# Sheet2.net
KiCad netlist of a schematic drawn in Altium Designer
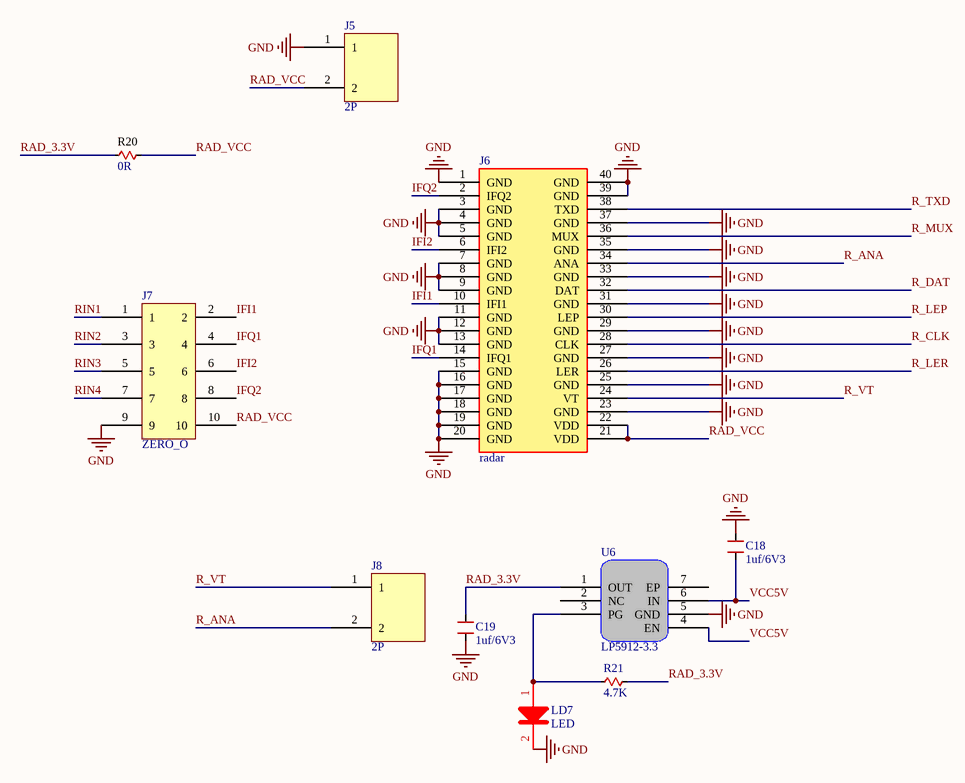
[diagram p0: Sheet2.SchDoc]

(export (version "E")
  (design (tool "Eeschema 10.0.6"))
  (components
    (comp (ref "C18")
      (value "1uf/6V3")
      (footprint "CAP0603")
      (description "Generic Capacitor")
      (libsource (lib "MZ7XB_Fun") (part "CAPACITOR_1UF"))
    )
    (comp (ref "C19")
      (value "1uf/6V3")
      (footprint "CAP0603")
      (description "Generic Capacitor")
      (libsource (lib "MZ7XB_Fun") (part "CAPACITOR_1UF"))
    )
    (comp (ref "J5") (value "2P") (footprint "2P") (libsource (lib "MZ7XB_Fun") (part "2P")))
    (comp (ref "J6") (value "radar") (footprint "BTB_40P_0.8_G") (libsource (lib "MZ7XB_Fun") (part "radar")))
    (comp (ref "J7") (value "ZERO_O") (footprint "2*5P") (libsource (lib "MZ7XB_Fun") (part "ZERO_O")))
    (comp (ref "J8") (value "2P") (footprint "2P") (libsource (lib "MZ7XB_Fun") (part "2P")))
    (comp (ref "LD7") (value "LED") (footprint "0603D") (libsource (lib "jinrylib") (part "LEDR")))
    (comp (ref "R20")
      (value "0R")
      (footprint "R0603")
      (description "Generic Resistor")
      (libsource (lib "Digilent") (part "RESISTOR"))
    )
    (comp (ref "R21")
      (value "4.7K")
      (footprint "R0603")
      (description "Generic Resistor")
      (libsource (lib "Digilent") (part "RESISTOR"))
    )
    (comp (ref "U6")
      (value "LP5912-3.3")
      (footprint "WSON-6_L2.0-W2.0-P0.65-TL-EP")
      (libsource (lib "MZ7XB_Fun") (part "LP5912-3.3"))
    )
  )
  (nets
    (net (code "1") (name "/IFI1") (class "Default")
      (node (ref "J6") (pin "10") (pinfunction "IFI1_10") (pintype "passive"))
      (node (ref "J7") (pin "2") (pinfunction "2_2") (pintype "passive"))
    )
    (net (code "2") (name "/IFI2") (class "Default")
      (node (ref "J6") (pin "6") (pinfunction "IFI2_6") (pintype "passive"))
      (node (ref "J7") (pin "6") (pinfunction "6_6") (pintype "passive"))
    )
    (net (code "3") (name "/IFQ1") (class "Default")
      (node (ref "J6") (pin "14") (pinfunction "IFQ1_14") (pintype "passive"))
      (node (ref "J7") (pin "4") (pinfunction "4_4") (pintype "passive"))
    )
    (net (code "4") (name "/IFQ2") (class "Default")
      (node (ref "J6") (pin "2") (pinfunction "IFQ2_2") (pintype "passive"))
      (node (ref "J7") (pin "8") (pinfunction "8_8") (pintype "passive"))
    )
    (net (code "5") (name "/RAD_3.3V") (class "Default")
      (node (ref "C19") (pin "1") (pinfunction "1_1") (pintype "passive"))
      (node (ref "R20") (pin "1") (pinfunction "1_1") (pintype "passive"))
      (node (ref "R21") (pin "2") (pinfunction "2_2") (pintype "passive"))
      (node (ref "U6") (pin "1") (pinfunction "OUT_1") (pintype "passive"))
    )
    (net (code "6") (name "/RAD_VCC") (class "Default")
      (node (ref "J5") (pin "2") (pinfunction "2_2") (pintype "passive"))
      (node (ref "J6") (pin "21") (pinfunction "VDD_21") (pintype "passive"))
      (node (ref "J6") (pin "22") (pinfunction "VDD_22") (pintype "passive"))
      (node (ref "J7") (pin "10") (pinfunction "10_10") (pintype "passive"))
      (node (ref "R20") (pin "2") (pinfunction "2_2") (pintype "passive"))
    )
    (net (code "7") (name "/RIN1") (class "Default")
      (node (ref "J7") (pin "1") (pinfunction "1_1") (pintype "passive"))
    )
    (net (code "8") (name "/RIN2") (class "Default")
      (node (ref "J7") (pin "3") (pinfunction "3_3") (pintype "passive"))
    )
    (net (code "9") (name "/RIN3") (class "Default")
      (node (ref "J7") (pin "5") (pinfunction "5_5") (pintype "passive"))
    )
    (net (code "10") (name "/RIN4") (class "Default")
      (node (ref "J7") (pin "7") (pinfunction "7_7") (pintype "passive"))
    )
    (net (code "11") (name "/R_ANA") (class "Default")
      (node (ref "J6") (pin "34") (pinfunction "ANA_34") (pintype "passive"))
      (node (ref "J8") (pin "2") (pinfunction "2_2") (pintype "passive"))
    )
    (net (code "12") (name "/R_CLK") (class "Default")
      (node (ref "J6") (pin "28") (pinfunction "CLK_28") (pintype "passive"))
    )
    (net (code "13") (name "/R_DAT") (class "Default")
      (node (ref "J6") (pin "32") (pinfunction "DAT_32") (pintype "passive"))
    )
    (net (code "14") (name "/R_LEP") (class "Default")
      (node (ref "J6") (pin "30") (pinfunction "LEP_30") (pintype "passive"))
    )
    (net (code "15") (name "/R_LER") (class "Default")
      (node (ref "J6") (pin "26") (pinfunction "LER_26") (pintype "passive"))
    )
    (net (code "16") (name "/R_MUX") (class "Default")
      (node (ref "J6") (pin "36") (pinfunction "MUX_36") (pintype "passive"))
    )
    (net (code "17") (name "/R_TXD") (class "Default")
      (node (ref "J6") (pin "38") (pinfunction "TXD_38") (pintype "passive"))
    )
    (net (code "18") (name "/R_VT") (class "Default")
      (node (ref "J6") (pin "24") (pinfunction "VT_24") (pintype "passive"))
      (node (ref "J8") (pin "1") (pinfunction "1_1") (pintype "passive"))
    )
    (net (code "19") (name "/VCC5V") (class "Default")
      (node (ref "C18") (pin "2") (pinfunction "2_2") (pintype "passive"))
      (node (ref "U6") (pin "4") (pinfunction "EN_4") (pintype "passive"))
      (node (ref "U6") (pin "6") (pinfunction "IN_6") (pintype "passive"))
    )
    (net (code "20") (name "GND") (class "Default")
      (node (ref "C18") (pin "1") (pinfunction "1_1") (pintype "passive"))
      (node (ref "C19") (pin "2") (pinfunction "2_2") (pintype "passive"))
      (node (ref "J5") (pin "1") (pinfunction "1_1") (pintype "passive"))
      (node (ref "J6") (pin "1") (pinfunction "GND_1") (pintype "passive"))
      (node (ref "J6") (pin "11") (pinfunction "GND_11") (pintype "passive"))
      (node (ref "J6") (pin "12") (pinfunction "GND_12") (pintype "passive"))
      (node (ref "J6") (pin "13") (pinfunction "GND_13") (pintype "passive"))
      (node (ref "J6") (pin "15") (pinfunction "GND_15") (pintype "passive"))
      (node (ref "J6") (pin "16") (pinfunction "GND_16") (pintype "passive"))
      (node (ref "J6") (pin "17") (pinfunction "GND_17") (pintype "passive"))
      (node (ref "J6") (pin "18") (pinfunction "GND_18") (pintype "passive"))
      (node (ref "J6") (pin "19") (pinfunction "GND_19") (pintype "passive"))
      (node (ref "J6") (pin "20") (pinfunction "GND_20") (pintype "passive"))
      (node (ref "J6") (pin "23") (pinfunction "GND_23") (pintype "passive"))
      (node (ref "J6") (pin "25") (pinfunction "GND_25") (pintype "passive"))
      (node (ref "J6") (pin "27") (pinfunction "GND_27") (pintype "passive"))
      (node (ref "J6") (pin "29") (pinfunction "GND_29") (pintype "passive"))
      (node (ref "J6") (pin "3") (pinfunction "GND_3") (pintype "passive"))
      (node (ref "J6") (pin "31") (pinfunction "GND_31") (pintype "passive"))
      (node (ref "J6") (pin "33") (pinfunction "GND_33") (pintype "passive"))
      (node (ref "J6") (pin "35") (pinfunction "GND_35") (pintype "passive"))
      (node (ref "J6") (pin "37") (pinfunction "GND_37") (pintype "passive"))
      (node (ref "J6") (pin "39") (pinfunction "GND_39") (pintype "passive"))
      (node (ref "J6") (pin "4") (pinfunction "GND_4") (pintype "passive"))
      (node (ref "J6") (pin "40") (pinfunction "GND_40") (pintype "passive"))
      (node (ref "J6") (pin "5") (pinfunction "GND_5") (pintype "passive"))
      (node (ref "J6") (pin "7") (pinfunction "GND_7") (pintype "passive"))
      (node (ref "J6") (pin "8") (pinfunction "GND_8") (pintype "passive"))
      (node (ref "J6") (pin "9") (pinfunction "GND_9") (pintype "passive"))
      (node (ref "J7") (pin "9") (pinfunction "9_9") (pintype "passive"))
      (node (ref "LD7") (pin "2") (pinfunction "2_2") (pintype "passive"))
      (node (ref "U6") (pin "5") (pinfunction "GND_5") (pintype "passive"))
    )
    (net (code "21") (name "Net-(U6-PG)") (class "Default")
      (node (ref "LD7") (pin "1") (pinfunction "1_1") (pintype "passive"))
      (node (ref "R21") (pin "1") (pinfunction "1_1") (pintype "passive"))
      (node (ref "U6") (pin "3") (pinfunction "PG_3") (pintype "passive"))
    )
    (net (code "22") (name "unconnected-(U6-EP-Pad7)") (class "Default")
      (node (ref "U6") (pin "7") (pinfunction "EP_7") (pintype "passive"))
    )
    (net (code "23") (name "unconnected-(U6-NC-Pad2)") (class "Default")
      (node (ref "U6") (pin "2") (pinfunction "NC_2") (pintype "passive"))
    )
  )
)
